# i2c_diff_passive.net
KiCad netlist of a schematic drawn in Altium Designer
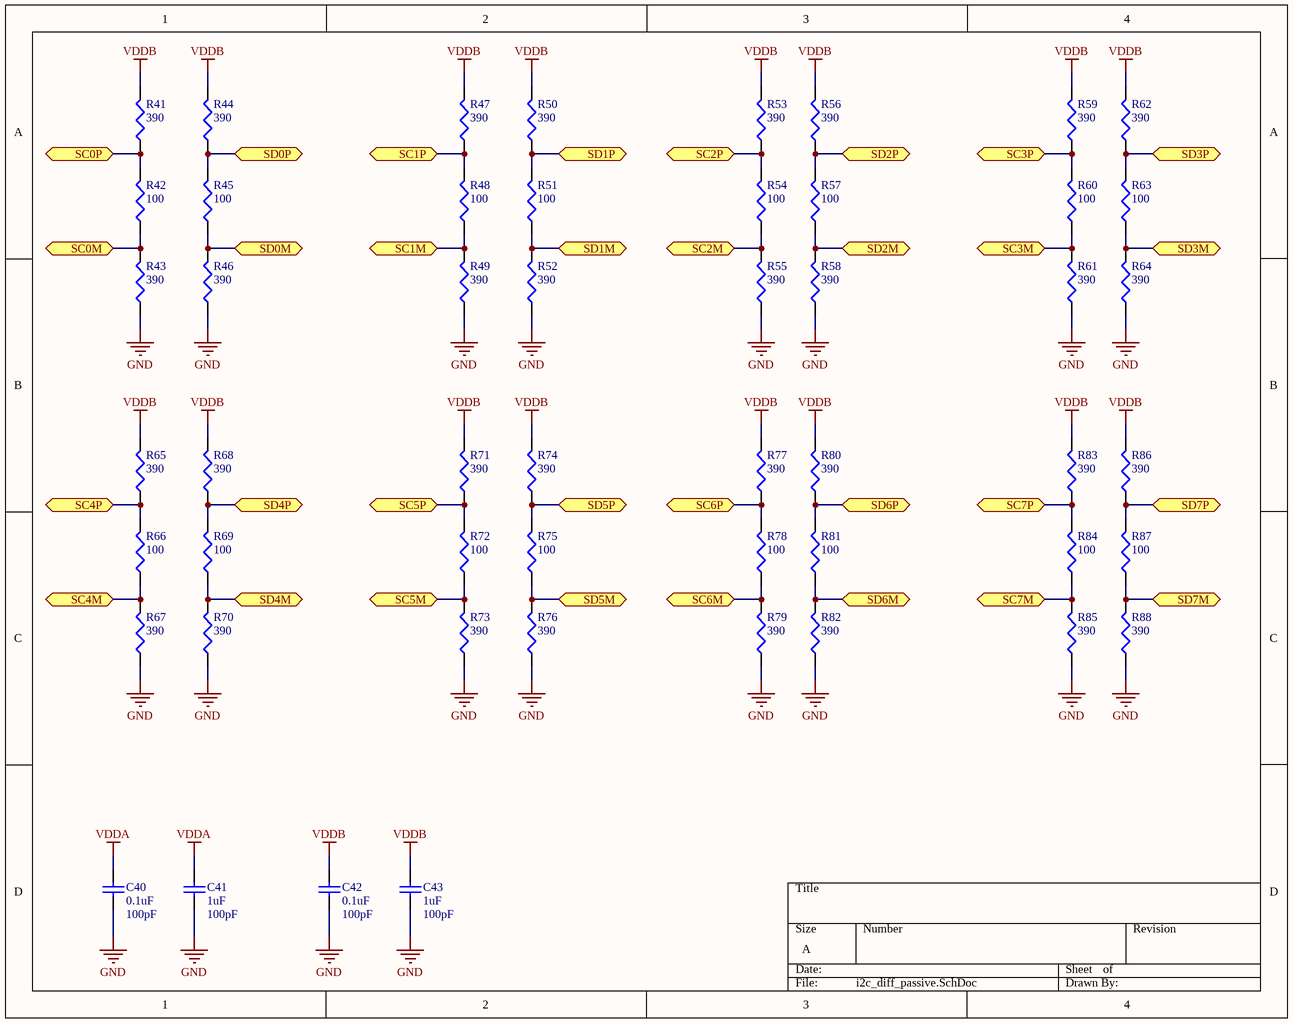
[diagram p0: i2c_diff_passive.SchDoc]

(export (version "E")
  (design (tool "Eeschema 10.0.6"))
  (components
    (comp (ref "C40")
      (value "0.1uF")
      (footprint "C1206")
      (description "Capacitor (Semiconductor SIM Model)")
      (fields (field (name "ALTIUM_VALUE") "100pF") (field (name "PUBLISHER") "Altium Limited"))
      (libsource (lib "Miscellaneous Devices") (part "Cap Semi"))
    )
    (comp (ref "C41")
      (value "1uF")
      (footprint "C1206")
      (description "Capacitor (Semiconductor SIM Model)")
      (fields (field (name "ALTIUM_VALUE") "100pF") (field (name "PUBLISHER") "Altium Limited"))
      (libsource (lib "Miscellaneous Devices") (part "Cap Semi"))
    )
    (comp (ref "C42")
      (value "0.1uF")
      (footprint "C1206")
      (description "Capacitor (Semiconductor SIM Model)")
      (fields (field (name "ALTIUM_VALUE") "100pF") (field (name "PUBLISHER") "Altium Limited"))
      (libsource (lib "Miscellaneous Devices") (part "Cap Semi"))
    )
    (comp (ref "C43")
      (value "1uF")
      (footprint "C1206")
      (description "Capacitor (Semiconductor SIM Model)")
      (fields (field (name "ALTIUM_VALUE") "100pF") (field (name "PUBLISHER") "Altium Limited"))
      (libsource (lib "Miscellaneous Devices") (part "Cap Semi"))
    )
    (comp (ref "R41")
      (value "390")
      (footprint "J1-0603")
      (description "Resistor")
      (fields (field (name "PUBLISHER") "Altium Limited"))
      (libsource (lib "Miscellaneous Devices") (part "Res3"))
    )
    (comp (ref "R42")
      (value "100")
      (footprint "J1-0603")
      (description "Resistor")
      (fields (field (name "PUBLISHER") "Altium Limited"))
      (libsource (lib "Miscellaneous Devices") (part "Res3"))
    )
    (comp (ref "R43")
      (value "390")
      (footprint "J1-0603")
      (description "Resistor")
      (fields (field (name "PUBLISHER") "Altium Limited"))
      (libsource (lib "Miscellaneous Devices") (part "Res3"))
    )
    (comp (ref "R44")
      (value "390")
      (footprint "J1-0603")
      (description "Resistor")
      (fields (field (name "PUBLISHER") "Altium Limited"))
      (libsource (lib "Miscellaneous Devices") (part "Res3"))
    )
    (comp (ref "R45")
      (value "100")
      (footprint "J1-0603")
      (description "Resistor")
      (fields (field (name "PUBLISHER") "Altium Limited"))
      (libsource (lib "Miscellaneous Devices") (part "Res3"))
    )
    (comp (ref "R46")
      (value "390")
      (footprint "J1-0603")
      (description "Resistor")
      (fields (field (name "PUBLISHER") "Altium Limited"))
      (libsource (lib "Miscellaneous Devices") (part "Res3"))
    )
    (comp (ref "R47")
      (value "390")
      (footprint "J1-0603")
      (description "Resistor")
      (fields (field (name "PUBLISHER") "Altium Limited"))
      (libsource (lib "Miscellaneous Devices") (part "Res3"))
    )
    (comp (ref "R48")
      (value "100")
      (footprint "J1-0603")
      (description "Resistor")
      (fields (field (name "PUBLISHER") "Altium Limited"))
      (libsource (lib "Miscellaneous Devices") (part "Res3"))
    )
    (comp (ref "R49")
      (value "390")
      (footprint "J1-0603")
      (description "Resistor")
      (fields (field (name "PUBLISHER") "Altium Limited"))
      (libsource (lib "Miscellaneous Devices") (part "Res3"))
    )
    (comp (ref "R50")
      (value "390")
      (footprint "J1-0603")
      (description "Resistor")
      (fields (field (name "PUBLISHER") "Altium Limited"))
      (libsource (lib "Miscellaneous Devices") (part "Res3"))
    )
    (comp (ref "R51")
      (value "100")
      (footprint "J1-0603")
      (description "Resistor")
      (fields (field (name "PUBLISHER") "Altium Limited"))
      (libsource (lib "Miscellaneous Devices") (part "Res3"))
    )
    (comp (ref "R52")
      (value "390")
      (footprint "J1-0603")
      (description "Resistor")
      (fields (field (name "PUBLISHER") "Altium Limited"))
      (libsource (lib "Miscellaneous Devices") (part "Res3"))
    )
    (comp (ref "R53")
      (value "390")
      (footprint "J1-0603")
      (description "Resistor")
      (fields (field (name "PUBLISHER") "Altium Limited"))
      (libsource (lib "Miscellaneous Devices") (part "Res3"))
    )
    (comp (ref "R54")
      (value "100")
      (footprint "J1-0603")
      (description "Resistor")
      (fields (field (name "PUBLISHER") "Altium Limited"))
      (libsource (lib "Miscellaneous Devices") (part "Res3"))
    )
    (comp (ref "R55")
      (value "390")
      (footprint "J1-0603")
      (description "Resistor")
      (fields (field (name "PUBLISHER") "Altium Limited"))
      (libsource (lib "Miscellaneous Devices") (part "Res3"))
    )
    (comp (ref "R56")
      (value "390")
      (footprint "J1-0603")
      (description "Resistor")
      (fields (field (name "PUBLISHER") "Altium Limited"))
      (libsource (lib "Miscellaneous Devices") (part "Res3"))
    )
    (comp (ref "R57")
      (value "100")
      (footprint "J1-0603")
      (description "Resistor")
      (fields (field (name "PUBLISHER") "Altium Limited"))
      (libsource (lib "Miscellaneous Devices") (part "Res3"))
    )
    (comp (ref "R58")
      (value "390")
      (footprint "J1-0603")
      (description "Resistor")
      (fields (field (name "PUBLISHER") "Altium Limited"))
      (libsource (lib "Miscellaneous Devices") (part "Res3"))
    )
    (comp (ref "R59")
      (value "390")
      (footprint "J1-0603")
      (description "Resistor")
      (fields (field (name "PUBLISHER") "Altium Limited"))
      (libsource (lib "Miscellaneous Devices") (part "Res3"))
    )
    (comp (ref "R60")
      (value "100")
      (footprint "J1-0603")
      (description "Resistor")
      (fields (field (name "PUBLISHER") "Altium Limited"))
      (libsource (lib "Miscellaneous Devices") (part "Res3"))
    )
    (comp (ref "R61")
      (value "390")
      (footprint "J1-0603")
      (description "Resistor")
      (fields (field (name "PUBLISHER") "Altium Limited"))
      (libsource (lib "Miscellaneous Devices") (part "Res3"))
    )
    (comp (ref "R62")
      (value "390")
      (footprint "J1-0603")
      (description "Resistor")
      (fields (field (name "PUBLISHER") "Altium Limited"))
      (libsource (lib "Miscellaneous Devices") (part "Res3"))
    )
    (comp (ref "R63")
      (value "100")
      (footprint "J1-0603")
      (description "Resistor")
      (fields (field (name "PUBLISHER") "Altium Limited"))
      (libsource (lib "Miscellaneous Devices") (part "Res3"))
    )
    (comp (ref "R64")
      (value "390")
      (footprint "J1-0603")
      (description "Resistor")
      (fields (field (name "PUBLISHER") "Altium Limited"))
      (libsource (lib "Miscellaneous Devices") (part "Res3"))
    )
    (comp (ref "R65")
      (value "390")
      (footprint "J1-0603")
      (description "Resistor")
      (fields (field (name "PUBLISHER") "Altium Limited"))
      (libsource (lib "Miscellaneous Devices") (part "Res3"))
    )
    (comp (ref "R66")
      (value "100")
      (footprint "J1-0603")
      (description "Resistor")
      (fields (field (name "PUBLISHER") "Altium Limited"))
      (libsource (lib "Miscellaneous Devices") (part "Res3"))
    )
    (comp (ref "R67")
      (value "390")
      (footprint "J1-0603")
      (description "Resistor")
      (fields (field (name "PUBLISHER") "Altium Limited"))
      (libsource (lib "Miscellaneous Devices") (part "Res3"))
    )
    (comp (ref "R68")
      (value "390")
      (footprint "J1-0603")
      (description "Resistor")
      (fields (field (name "PUBLISHER") "Altium Limited"))
      (libsource (lib "Miscellaneous Devices") (part "Res3"))
    )
    (comp (ref "R69")
      (value "100")
      (footprint "J1-0603")
      (description "Resistor")
      (fields (field (name "PUBLISHER") "Altium Limited"))
      (libsource (lib "Miscellaneous Devices") (part "Res3"))
    )
    (comp (ref "R70")
      (value "390")
      (footprint "J1-0603")
      (description "Resistor")
      (fields (field (name "PUBLISHER") "Altium Limited"))
      (libsource (lib "Miscellaneous Devices") (part "Res3"))
    )
    (comp (ref "R71")
      (value "390")
      (footprint "J1-0603")
      (description "Resistor")
      (fields (field (name "PUBLISHER") "Altium Limited"))
      (libsource (lib "Miscellaneous Devices") (part "Res3"))
    )
    (comp (ref "R72")
      (value "100")
      (footprint "J1-0603")
      (description "Resistor")
      (fields (field (name "PUBLISHER") "Altium Limited"))
      (libsource (lib "Miscellaneous Devices") (part "Res3"))
    )
    (comp (ref "R73")
      (value "390")
      (footprint "J1-0603")
      (description "Resistor")
      (fields (field (name "PUBLISHER") "Altium Limited"))
      (libsource (lib "Miscellaneous Devices") (part "Res3"))
    )
    (comp (ref "R74")
      (value "390")
      (footprint "J1-0603")
      (description "Resistor")
      (fields (field (name "PUBLISHER") "Altium Limited"))
      (libsource (lib "Miscellaneous Devices") (part "Res3"))
    )
    (comp (ref "R75")
      (value "100")
      (footprint "J1-0603")
      (description "Resistor")
      (fields (field (name "PUBLISHER") "Altium Limited"))
      (libsource (lib "Miscellaneous Devices") (part "Res3"))
    )
    (comp (ref "R76")
      (value "390")
      (footprint "J1-0603")
      (description "Resistor")
      (fields (field (name "PUBLISHER") "Altium Limited"))
      (libsource (lib "Miscellaneous Devices") (part "Res3"))
    )
    (comp (ref "R77")
      (value "390")
      (footprint "J1-0603")
      (description "Resistor")
      (fields (field (name "PUBLISHER") "Altium Limited"))
      (libsource (lib "Miscellaneous Devices") (part "Res3"))
    )
    (comp (ref "R78")
      (value "100")
      (footprint "J1-0603")
      (description "Resistor")
      (fields (field (name "PUBLISHER") "Altium Limited"))
      (libsource (lib "Miscellaneous Devices") (part "Res3"))
    )
    (comp (ref "R79")
      (value "390")
      (footprint "J1-0603")
      (description "Resistor")
      (fields (field (name "PUBLISHER") "Altium Limited"))
      (libsource (lib "Miscellaneous Devices") (part "Res3"))
    )
    (comp (ref "R80")
      (value "390")
      (footprint "J1-0603")
      (description "Resistor")
      (fields (field (name "PUBLISHER") "Altium Limited"))
      (libsource (lib "Miscellaneous Devices") (part "Res3"))
    )
    (comp (ref "R81")
      (value "100")
      (footprint "J1-0603")
      (description "Resistor")
      (fields (field (name "PUBLISHER") "Altium Limited"))
      (libsource (lib "Miscellaneous Devices") (part "Res3"))
    )
    (comp (ref "R82")
      (value "390")
      (footprint "J1-0603")
      (description "Resistor")
      (fields (field (name "PUBLISHER") "Altium Limited"))
      (libsource (lib "Miscellaneous Devices") (part "Res3"))
    )
    (comp (ref "R83")
      (value "390")
      (footprint "J1-0603")
      (description "Resistor")
      (fields (field (name "PUBLISHER") "Altium Limited"))
      (libsource (lib "Miscellaneous Devices") (part "Res3"))
    )
    (comp (ref "R84")
      (value "100")
      (footprint "J1-0603")
      (description "Resistor")
      (fields (field (name "PUBLISHER") "Altium Limited"))
      (libsource (lib "Miscellaneous Devices") (part "Res3"))
    )
    (comp (ref "R85")
      (value "390")
      (footprint "J1-0603")
      (description "Resistor")
      (fields (field (name "PUBLISHER") "Altium Limited"))
      (libsource (lib "Miscellaneous Devices") (part "Res3"))
    )
    (comp (ref "R86")
      (value "390")
      (footprint "J1-0603")
      (description "Resistor")
      (fields (field (name "PUBLISHER") "Altium Limited"))
      (libsource (lib "Miscellaneous Devices") (part "Res3"))
    )
    (comp (ref "R87")
      (value "100")
      (footprint "J1-0603")
      (description "Resistor")
      (fields (field (name "PUBLISHER") "Altium Limited"))
      (libsource (lib "Miscellaneous Devices") (part "Res3"))
    )
    (comp (ref "R88")
      (value "390")
      (footprint "J1-0603")
      (description "Resistor")
      (fields (field (name "PUBLISHER") "Altium Limited"))
      (libsource (lib "Miscellaneous Devices") (part "Res3"))
    )
  )
  (nets
    (net (code "1") (name "/SC0M") (class "Default")
      (node (ref "R42") (pin "1") (pinfunction "1_1") (pintype "passive"))
      (node (ref "R43") (pin "2") (pinfunction "2_2") (pintype "passive"))
    )
    (net (code "2") (name "/SC0P") (class "Default")
      (node (ref "R41") (pin "1") (pinfunction "1_1") (pintype "passive"))
      (node (ref "R42") (pin "2") (pinfunction "2_2") (pintype "passive"))
    )
    (net (code "3") (name "/SC1M") (class "Default")
      (node (ref "R48") (pin "1") (pinfunction "1_1") (pintype "passive"))
      (node (ref "R49") (pin "2") (pinfunction "2_2") (pintype "passive"))
    )
    (net (code "4") (name "/SC1P") (class "Default")
      (node (ref "R47") (pin "1") (pinfunction "1_1") (pintype "passive"))
      (node (ref "R48") (pin "2") (pinfunction "2_2") (pintype "passive"))
    )
    (net (code "5") (name "/SC2M") (class "Default")
      (node (ref "R54") (pin "1") (pinfunction "1_1") (pintype "passive"))
      (node (ref "R55") (pin "2") (pinfunction "2_2") (pintype "passive"))
    )
    (net (code "6") (name "/SC2P") (class "Default")
      (node (ref "R53") (pin "1") (pinfunction "1_1") (pintype "passive"))
      (node (ref "R54") (pin "2") (pinfunction "2_2") (pintype "passive"))
    )
    (net (code "7") (name "/SC3M") (class "Default")
      (node (ref "R60") (pin "1") (pinfunction "1_1") (pintype "passive"))
      (node (ref "R61") (pin "2") (pinfunction "2_2") (pintype "passive"))
    )
    (net (code "8") (name "/SC3P") (class "Default")
      (node (ref "R59") (pin "1") (pinfunction "1_1") (pintype "passive"))
      (node (ref "R60") (pin "2") (pinfunction "2_2") (pintype "passive"))
    )
    (net (code "9") (name "/SC4M") (class "Default")
      (node (ref "R66") (pin "1") (pinfunction "1_1") (pintype "passive"))
      (node (ref "R67") (pin "2") (pinfunction "2_2") (pintype "passive"))
    )
    (net (code "10") (name "/SC4P") (class "Default")
      (node (ref "R65") (pin "1") (pinfunction "1_1") (pintype "passive"))
      (node (ref "R66") (pin "2") (pinfunction "2_2") (pintype "passive"))
    )
    (net (code "11") (name "/SC5M") (class "Default")
      (node (ref "R72") (pin "1") (pinfunction "1_1") (pintype "passive"))
      (node (ref "R73") (pin "2") (pinfunction "2_2") (pintype "passive"))
    )
    (net (code "12") (name "/SC5P") (class "Default")
      (node (ref "R71") (pin "1") (pinfunction "1_1") (pintype "passive"))
      (node (ref "R72") (pin "2") (pinfunction "2_2") (pintype "passive"))
    )
    (net (code "13") (name "/SC6M") (class "Default")
      (node (ref "R78") (pin "1") (pinfunction "1_1") (pintype "passive"))
      (node (ref "R79") (pin "2") (pinfunction "2_2") (pintype "passive"))
    )
    (net (code "14") (name "/SC6P") (class "Default")
      (node (ref "R77") (pin "1") (pinfunction "1_1") (pintype "passive"))
      (node (ref "R78") (pin "2") (pinfunction "2_2") (pintype "passive"))
    )
    (net (code "15") (name "/SC7M") (class "Default")
      (node (ref "R84") (pin "1") (pinfunction "1_1") (pintype "passive"))
      (node (ref "R85") (pin "2") (pinfunction "2_2") (pintype "passive"))
    )
    (net (code "16") (name "/SC7P") (class "Default")
      (node (ref "R83") (pin "1") (pinfunction "1_1") (pintype "passive"))
      (node (ref "R84") (pin "2") (pinfunction "2_2") (pintype "passive"))
    )
    (net (code "17") (name "/SD0M") (class "Default")
      (node (ref "R45") (pin "1") (pinfunction "1_1") (pintype "passive"))
      (node (ref "R46") (pin "2") (pinfunction "2_2") (pintype "passive"))
    )
    (net (code "18") (name "/SD0P") (class "Default")
      (node (ref "R44") (pin "1") (pinfunction "1_1") (pintype "passive"))
      (node (ref "R45") (pin "2") (pinfunction "2_2") (pintype "passive"))
    )
    (net (code "19") (name "/SD1M") (class "Default")
      (node (ref "R51") (pin "1") (pinfunction "1_1") (pintype "passive"))
      (node (ref "R52") (pin "2") (pinfunction "2_2") (pintype "passive"))
    )
    (net (code "20") (name "/SD1P") (class "Default")
      (node (ref "R50") (pin "1") (pinfunction "1_1") (pintype "passive"))
      (node (ref "R51") (pin "2") (pinfunction "2_2") (pintype "passive"))
    )
    (net (code "21") (name "/SD2M") (class "Default")
      (node (ref "R57") (pin "1") (pinfunction "1_1") (pintype "passive"))
      (node (ref "R58") (pin "2") (pinfunction "2_2") (pintype "passive"))
    )
    (net (code "22") (name "/SD2P") (class "Default")
      (node (ref "R56") (pin "1") (pinfunction "1_1") (pintype "passive"))
      (node (ref "R57") (pin "2") (pinfunction "2_2") (pintype "passive"))
    )
    (net (code "23") (name "/SD3M") (class "Default")
      (node (ref "R63") (pin "1") (pinfunction "1_1") (pintype "passive"))
      (node (ref "R64") (pin "2") (pinfunction "2_2") (pintype "passive"))
    )
    (net (code "24") (name "/SD3P") (class "Default")
      (node (ref "R62") (pin "1") (pinfunction "1_1") (pintype "passive"))
      (node (ref "R63") (pin "2") (pinfunction "2_2") (pintype "passive"))
    )
    (net (code "25") (name "/SD4M") (class "Default")
      (node (ref "R69") (pin "1") (pinfunction "1_1") (pintype "passive"))
      (node (ref "R70") (pin "2") (pinfunction "2_2") (pintype "passive"))
    )
    (net (code "26") (name "/SD4P") (class "Default")
      (node (ref "R68") (pin "1") (pinfunction "1_1") (pintype "passive"))
      (node (ref "R69") (pin "2") (pinfunction "2_2") (pintype "passive"))
    )
    (net (code "27") (name "/SD5M") (class "Default")
      (node (ref "R75") (pin "1") (pinfunction "1_1") (pintype "passive"))
      (node (ref "R76") (pin "2") (pinfunction "2_2") (pintype "passive"))
    )
    (net (code "28") (name "/SD5P") (class "Default")
      (node (ref "R74") (pin "1") (pinfunction "1_1") (pintype "passive"))
      (node (ref "R75") (pin "2") (pinfunction "2_2") (pintype "passive"))
    )
    (net (code "29") (name "/SD6M") (class "Default")
      (node (ref "R81") (pin "1") (pinfunction "1_1") (pintype "passive"))
      (node (ref "R82") (pin "2") (pinfunction "2_2") (pintype "passive"))
    )
    (net (code "30") (name "/SD6P") (class "Default")
      (node (ref "R80") (pin "1") (pinfunction "1_1") (pintype "passive"))
      (node (ref "R81") (pin "2") (pinfunction "2_2") (pintype "passive"))
    )
    (net (code "31") (name "/SD7M") (class "Default")
      (node (ref "R87") (pin "1") (pinfunction "1_1") (pintype "passive"))
      (node (ref "R88") (pin "2") (pinfunction "2_2") (pintype "passive"))
    )
    (net (code "32") (name "/SD7P") (class "Default")
      (node (ref "R86") (pin "1") (pinfunction "1_1") (pintype "passive"))
      (node (ref "R87") (pin "2") (pinfunction "2_2") (pintype "passive"))
    )
    (net (code "33") (name "GND") (class "Default")
      (node (ref "C40") (pin "1") (pinfunction "1_1") (pintype "passive"))
      (node (ref "C41") (pin "1") (pinfunction "1_1") (pintype "passive"))
      (node (ref "C42") (pin "1") (pinfunction "1_1") (pintype "passive"))
      (node (ref "C43") (pin "1") (pinfunction "1_1") (pintype "passive"))
      (node (ref "R43") (pin "1") (pinfunction "1_1") (pintype "passive"))
      (node (ref "R46") (pin "1") (pinfunction "1_1") (pintype "passive"))
      (node (ref "R49") (pin "1") (pinfunction "1_1") (pintype "passive"))
      (node (ref "R52") (pin "1") (pinfunction "1_1") (pintype "passive"))
      (node (ref "R55") (pin "1") (pinfunction "1_1") (pintype "passive"))
      (node (ref "R58") (pin "1") (pinfunction "1_1") (pintype "passive"))
      (node (ref "R61") (pin "1") (pinfunction "1_1") (pintype "passive"))
      (node (ref "R64") (pin "1") (pinfunction "1_1") (pintype "passive"))
      (node (ref "R67") (pin "1") (pinfunction "1_1") (pintype "passive"))
      (node (ref "R70") (pin "1") (pinfunction "1_1") (pintype "passive"))
      (node (ref "R73") (pin "1") (pinfunction "1_1") (pintype "passive"))
      (node (ref "R76") (pin "1") (pinfunction "1_1") (pintype "passive"))
      (node (ref "R79") (pin "1") (pinfunction "1_1") (pintype "passive"))
      (node (ref "R82") (pin "1") (pinfunction "1_1") (pintype "passive"))
      (node (ref "R85") (pin "1") (pinfunction "1_1") (pintype "passive"))
      (node (ref "R88") (pin "1") (pinfunction "1_1") (pintype "passive"))
    )
    (net (code "34") (name "VDDA") (class "Default")
      (node (ref "C40") (pin "2") (pinfunction "2_2") (pintype "passive"))
      (node (ref "C41") (pin "2") (pinfunction "2_2") (pintype "passive"))
    )
    (net (code "35") (name "VDDB") (class "Default")
      (node (ref "C42") (pin "2") (pinfunction "2_2") (pintype "passive"))
      (node (ref "C43") (pin "2") (pinfunction "2_2") (pintype "passive"))
      (node (ref "R41") (pin "2") (pinfunction "2_2") (pintype "passive"))
      (node (ref "R44") (pin "2") (pinfunction "2_2") (pintype "passive"))
      (node (ref "R47") (pin "2") (pinfunction "2_2") (pintype "passive"))
      (node (ref "R50") (pin "2") (pinfunction "2_2") (pintype "passive"))
      (node (ref "R53") (pin "2") (pinfunction "2_2") (pintype "passive"))
      (node (ref "R56") (pin "2") (pinfunction "2_2") (pintype "passive"))
      (node (ref "R59") (pin "2") (pinfunction "2_2") (pintype "passive"))
      (node (ref "R62") (pin "2") (pinfunction "2_2") (pintype "passive"))
      (node (ref "R65") (pin "2") (pinfunction "2_2") (pintype "passive"))
      (node (ref "R68") (pin "2") (pinfunction "2_2") (pintype "passive"))
      (node (ref "R71") (pin "2") (pinfunction "2_2") (pintype "passive"))
      (node (ref "R74") (pin "2") (pinfunction "2_2") (pintype "passive"))
      (node (ref "R77") (pin "2") (pinfunction "2_2") (pintype "passive"))
      (node (ref "R80") (pin "2") (pinfunction "2_2") (pintype "passive"))
      (node (ref "R83") (pin "2") (pinfunction "2_2") (pintype "passive"))
      (node (ref "R86") (pin "2") (pinfunction "2_2") (pintype "passive"))
    )
  )
)
